# isolator_si8662.net
KiCad netlist of a schematic drawn in Altium Designer
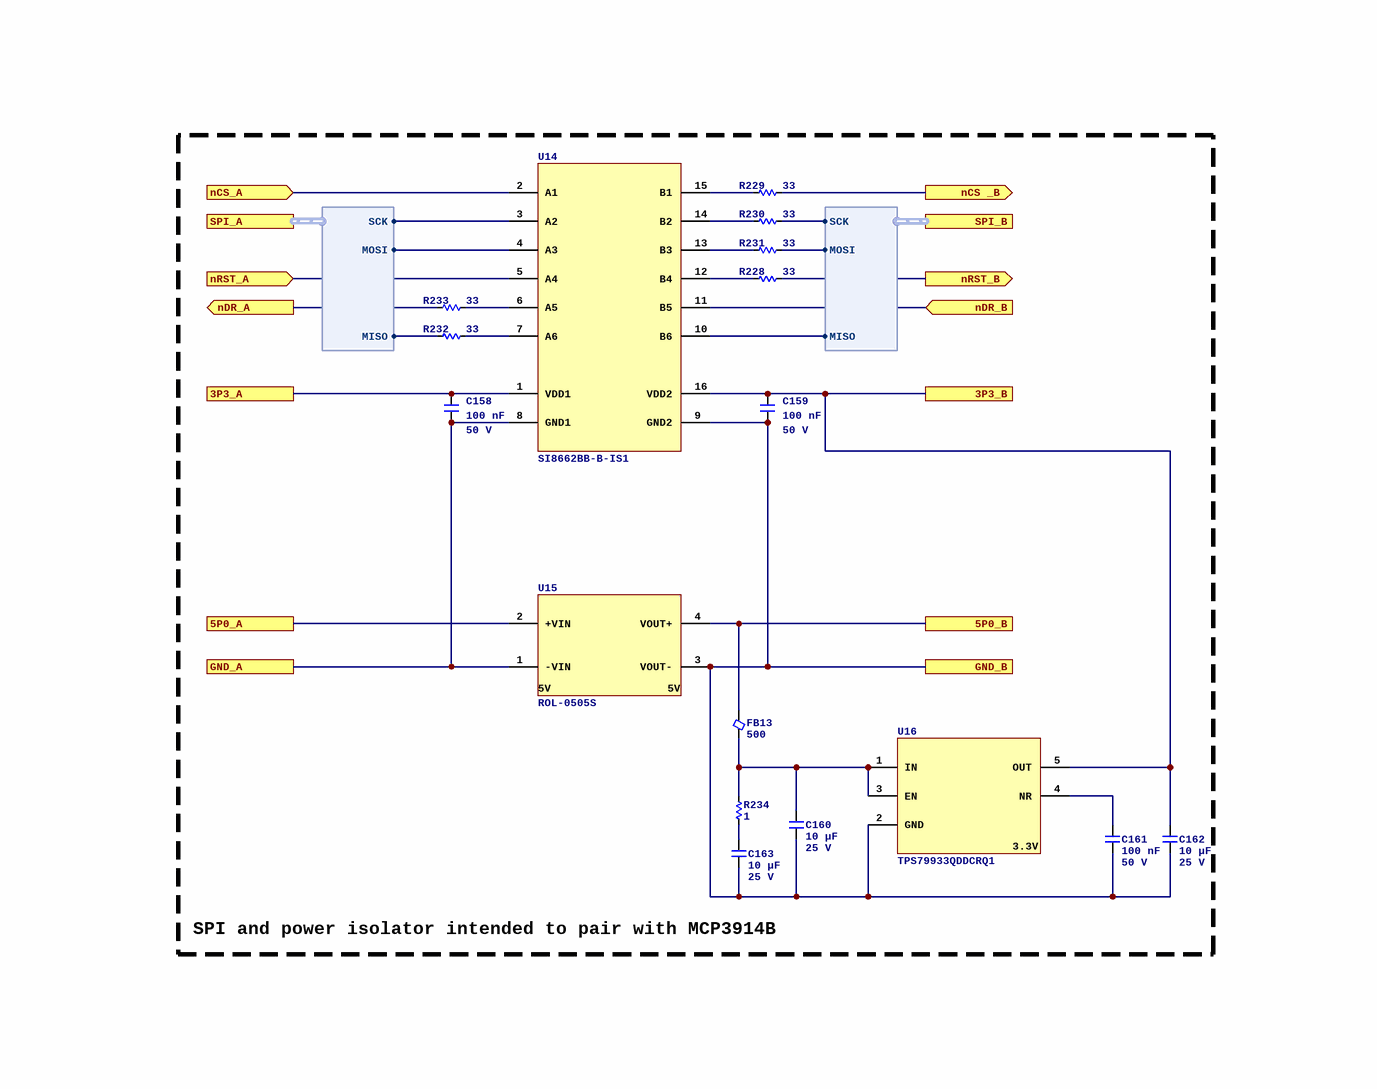
[diagram p0: isolator_si8662.SchDoc]

(export (version "E")
  (design (tool "Eeschema 10.0.6"))
  (components
    (comp (ref "C158")
      (value "CL05B104KB54PNC")
      (footprint "C0402")
      (fields
        (field (name "CAPACITANCE") "100 nF")
        (field (name "MANUFACTURER") "Samsung Electro-Mechanics")
        (field (name "VOLTAGE RATING") "50 V")
      )
      (libsource (lib "database") (part "__template_cap"))
    )
    (comp (ref "C159")
      (value "CL05B104KB54PNC")
      (footprint "C0402")
      (fields
        (field (name "CAPACITANCE") "100 nF")
        (field (name "MANUFACTURER") "Samsung Electro-Mechanics")
        (field (name "VOLTAGE RATING") "50 V")
      )
      (libsource (lib "database") (part "__template_cap"))
    )
    (comp (ref "C160")
      (value "CL10A106MA8NRNC")
      (footprint "C0603")
      (fields
        (field (name "CAPACITANCE") "10 µF")
        (field (name "MANUFACTURER") "Samsung Electro-Mechanics")
        (field (name "VOLTAGE RATING") "25 V")
      )
      (libsource (lib "database") (part "__template_cap"))
    )
    (comp (ref "C161")
      (value "CL05B104KB54PNC")
      (footprint "C0402")
      (fields
        (field (name "CAPACITANCE") "100 nF")
        (field (name "MANUFACTURER") "Samsung Electro-Mechanics")
        (field (name "VOLTAGE RATING") "50 V")
      )
      (libsource (lib "database") (part "__template_cap"))
    )
    (comp (ref "C162")
      (value "CL21B106KAYQNNE")
      (footprint "C0805")
      (fields
        (field (name "CAPACITANCE") "10 µF")
        (field (name "MANUFACTURER") "Samsung Electro-Mechanics")
        (field (name "VOLTAGE RATING") "25 V")
      )
      (libsource (lib "database") (part "__template_cap"))
    )
    (comp (ref "C163")
      (value "CL21B106KAYQNNE")
      (footprint "C0805")
      (fields
        (field (name "CAPACITANCE") "10 µF")
        (field (name "MANUFACTURER") "Samsung Electro-Mechanics")
        (field (name "VOLTAGE RATING") "25 V")
      )
      (libsource (lib "database") (part "__template_cap"))
    )
    (comp (ref "FB13")
      (value "BLM15AX601SN1D")
      (footprint "FB0402")
      (fields (field (name "MANUFACTURER") "Murata Electronics") (field (name "CURRENT RATING (MA)") "500"))
      (libsource (lib "database") (part "__template_fb"))
    )
    (comp (ref "R228")
      (value "33")
      (footprint "R0402")
      (fields
        (field (name "TOLERANCE") "1%")
        (field (name "MANUFACTURER PART NUMBER") "0402WGF330JTCE")
        (field (name "MANUFACTURER") "UNI-ROYAL(Uniroyal Elec)")
      )
      (libsource (lib "database") (part "__template_resistor"))
    )
    (comp (ref "R229")
      (value "33")
      (footprint "R0402")
      (fields
        (field (name "TOLERANCE") "1%")
        (field (name "MANUFACTURER PART NUMBER") "0402WGF330JTCE")
        (field (name "MANUFACTURER") "UNI-ROYAL(Uniroyal Elec)")
      )
      (libsource (lib "database") (part "__template_resistor"))
    )
    (comp (ref "R230")
      (value "33")
      (footprint "R0402")
      (fields
        (field (name "TOLERANCE") "1%")
        (field (name "MANUFACTURER PART NUMBER") "0402WGF330JTCE")
        (field (name "MANUFACTURER") "UNI-ROYAL(Uniroyal Elec)")
      )
      (libsource (lib "database") (part "__template_resistor"))
    )
    (comp (ref "R231")
      (value "33")
      (footprint "R0402")
      (fields
        (field (name "TOLERANCE") "1%")
        (field (name "MANUFACTURER PART NUMBER") "0402WGF330JTCE")
        (field (name "MANUFACTURER") "UNI-ROYAL(Uniroyal Elec)")
      )
      (libsource (lib "database") (part "__template_resistor"))
    )
    (comp (ref "R232")
      (value "33")
      (footprint "R0402")
      (fields
        (field (name "TOLERANCE") "1%")
        (field (name "MANUFACTURER PART NUMBER") "0402WGF330JTCE")
        (field (name "MANUFACTURER") "UNI-ROYAL(Uniroyal Elec)")
      )
      (libsource (lib "database") (part "__template_resistor"))
    )
    (comp (ref "R233")
      (value "33")
      (footprint "R0402")
      (fields
        (field (name "TOLERANCE") "1%")
        (field (name "MANUFACTURER PART NUMBER") "0402WGF330JTCE")
        (field (name "MANUFACTURER") "UNI-ROYAL(Uniroyal Elec)")
      )
      (libsource (lib "database") (part "__template_resistor"))
    )
    (comp (ref "R234")
      (value "1")
      (footprint "R0402")
      (fields
        (field (name "TOLERANCE") "1%")
        (field (name "MANUFACTURER PART NUMBER") "CRCW04021R00FKED")
        (field (name "MANUFACTURER") "Vishay Intertech")
      )
      (libsource (lib "database") (part "__template_resistor"))
    )
    (comp (ref "U14")
      (value "SI8662BB-B-IS1")
      (footprint "16SOIC150")
      (description "6-ch 2.5kV Isolator, 150M, 4/2, NB SOIC16, lead free")
      (fields (field (name "MANUFACTURER") "Skyworks Solutions"))
      (libsource (lib "database") (part "SI8662BB-B-IS1"))
    )
    (comp (ref "U15")
      (value "ROL-0505S")
      (footprint "4SIP")
      (description "5V to 5V isolated power supply module")
      (fields (field (name "MANUFACTURER") "Recom"))
      (libsource (lib "database") (part "ROL-0505S"))
    )
    (comp (ref "U16")
      (value "TPS79933QDDCRQ1")
      (footprint "5SOT23")
      (description "Fixed Positive LDO Regulator, 3.3V, 0.16V Dropout, BICMOS, PDSO5")
      (fields (field (name "MANUFACTURER") "Texas Instruments"))
      (libsource (lib "database") (part "TPS79933QDDCRQ1"))
    )
  )
  (nets
    (net (code "2") (name "/3P3_A") (class "Default")
      (node (ref "C158") (pin "1") (pintype "passive"))
      (node (ref "U14") (pin "1") (pinfunction "VDD1_1") (pintype "passive"))
    )
    (net (code "3") (name "/3P3_B") (class "Default")
      (node (ref "C159") (pin "1") (pintype "passive"))
      (node (ref "C162") (pin "1") (pintype "passive"))
      (node (ref "U14") (pin "16") (pinfunction "VDD2_16") (pintype "passive"))
      (node (ref "U16") (pin "5") (pinfunction "OUT_5") (pintype "passive"))
    )
    (net (code "4") (name "/5P0_A") (class "Default")
      (node (ref "U15") (pin "2") (pinfunction "+VIN_2") (pintype "passive"))
    )
    (net (code "5") (name "/5P0_B") (class "Default")
      (node (ref "FB13") (pin "2") (pintype "passive"))
      (node (ref "U15") (pin "4") (pinfunction "VOUT+_4") (pintype "passive"))
    )
    (net (code "6") (name "/GND_A") (class "Default")
      (node (ref "C158") (pin "2") (pintype "passive"))
      (node (ref "U14") (pin "8") (pinfunction "GND1_8") (pintype "passive"))
      (node (ref "U15") (pin "1") (pinfunction "-VIN_1") (pintype "passive"))
    )
    (net (code "7") (name "/GND_B") (class "Default")
      (node (ref "C159") (pin "2") (pintype "passive"))
      (node (ref "C160") (pin "2") (pintype "passive"))
      (node (ref "C161") (pin "2") (pintype "passive"))
      (node (ref "C162") (pin "2") (pintype "passive"))
      (node (ref "C163") (pin "2") (pintype "passive"))
      (node (ref "U14") (pin "9") (pinfunction "GND2_9") (pintype "passive"))
      (node (ref "U15") (pin "3") (pinfunction "VOUT-_3") (pintype "passive"))
      (node (ref "U16") (pin "2") (pinfunction "GND_2") (pintype "passive"))
    )
    (net (code "8") (name "/nCS _B") (class "Default") (node (ref "R229") (pin "1") (pintype "passive")))
    (net (code "9") (name "/nCS_A") (class "Default")
      (node (ref "U14") (pin "2") (pinfunction "A1_2") (pintype "passive"))
    )
    (net (code "10") (name "/nDR_A") (class "Default") (node (ref "R233") (pin "2") (pintype "passive")))
    (net (code "11") (name "/nDR_B") (class "Default")
      (node (ref "U14") (pin "11") (pinfunction "B5_11") (pintype "passive"))
    )
    (net (code "12") (name "/nRST_A") (class "Default")
      (node (ref "U14") (pin "5") (pinfunction "A4_5") (pintype "passive"))
    )
    (net (code "13") (name "/nRST_B") (class "Default") (node (ref "R228") (pin "1") (pintype "passive")))
    (net (code "15") (name "Net-(C163-Pad1)") (class "Default")
      (node (ref "C163") (pin "1") (pintype "passive"))
      (node (ref "R234") (pin "1") (pintype "passive"))
    )
    (net (code "16") (name "Net-(U14-A5)") (class "Default")
      (node (ref "R233") (pin "1") (pintype "passive"))
      (node (ref "U14") (pin "6") (pinfunction "A5_6") (pintype "passive"))
    )
    (net (code "17") (name "Net-(U14-A6)") (class "Default")
      (node (ref "R232") (pin "1") (pintype "passive"))
      (node (ref "U14") (pin "7") (pinfunction "A6_7") (pintype "passive"))
    )
    (net (code "18") (name "Net-(U14-B1)") (class "Default")
      (node (ref "R229") (pin "2") (pintype "passive"))
      (node (ref "U14") (pin "15") (pinfunction "B1_15") (pintype "passive"))
    )
    (net (code "19") (name "Net-(U14-B2)") (class "Default")
      (node (ref "R230") (pin "2") (pintype "passive"))
      (node (ref "U14") (pin "14") (pinfunction "B2_14") (pintype "passive"))
    )
    (net (code "20") (name "Net-(U14-B3)") (class "Default")
      (node (ref "R231") (pin "2") (pintype "passive"))
      (node (ref "U14") (pin "13") (pinfunction "B3_13") (pintype "passive"))
    )
    (net (code "21") (name "Net-(U14-B4)") (class "Default")
      (node (ref "R228") (pin "2") (pintype "passive"))
      (node (ref "U14") (pin "12") (pinfunction "B4_12") (pintype "passive"))
    )
    (net (code "22") (name "Net-(U16-EN)") (class "Default")
      (node (ref "C160") (pin "1") (pintype "passive"))
      (node (ref "FB13") (pin "1") (pintype "passive"))
      (node (ref "R234") (pin "2") (pintype "passive"))
      (node (ref "U16") (pin "1") (pinfunction "IN_1") (pintype "passive"))
      (node (ref "U16") (pin "3") (pinfunction "EN_3") (pintype "passive"))
    )
    (net (code "23") (name "Net-(U16-NR)") (class "Default")
      (node (ref "C161") (pin "1") (pintype "passive"))
      (node (ref "U16") (pin "4") (pinfunction "NR_4") (pintype "passive"))
    )
    (net (code "24") (name "unconnected-(R230-Pad1)") (class "Default")
      (node (ref "R230") (pin "1") (pintype "passive"))
    )
    (net (code "25") (name "unconnected-(R231-Pad1)") (class "Default")
      (node (ref "R231") (pin "1") (pintype "passive"))
    )
    (net (code "26") (name "unconnected-(R232-Pad2)") (class "Default")
      (node (ref "R232") (pin "2") (pintype "passive"))
    )
    (net (code "27") (name "unconnected-(U14-A2-Pad3)") (class "Default")
      (node (ref "U14") (pin "3") (pinfunction "A2_3") (pintype "passive"))
    )
    (net (code "28") (name "unconnected-(U14-A3-Pad4)") (class "Default")
      (node (ref "U14") (pin "4") (pinfunction "A3_4") (pintype "passive"))
    )
    (net (code "29") (name "unconnected-(U14-B6-Pad10)") (class "Default")
      (node (ref "U14") (pin "10") (pinfunction "B6_10") (pintype "passive"))
    )
  )
)
